# seismometer.net
KiCad netlist of a schematic drawn in EAGLE
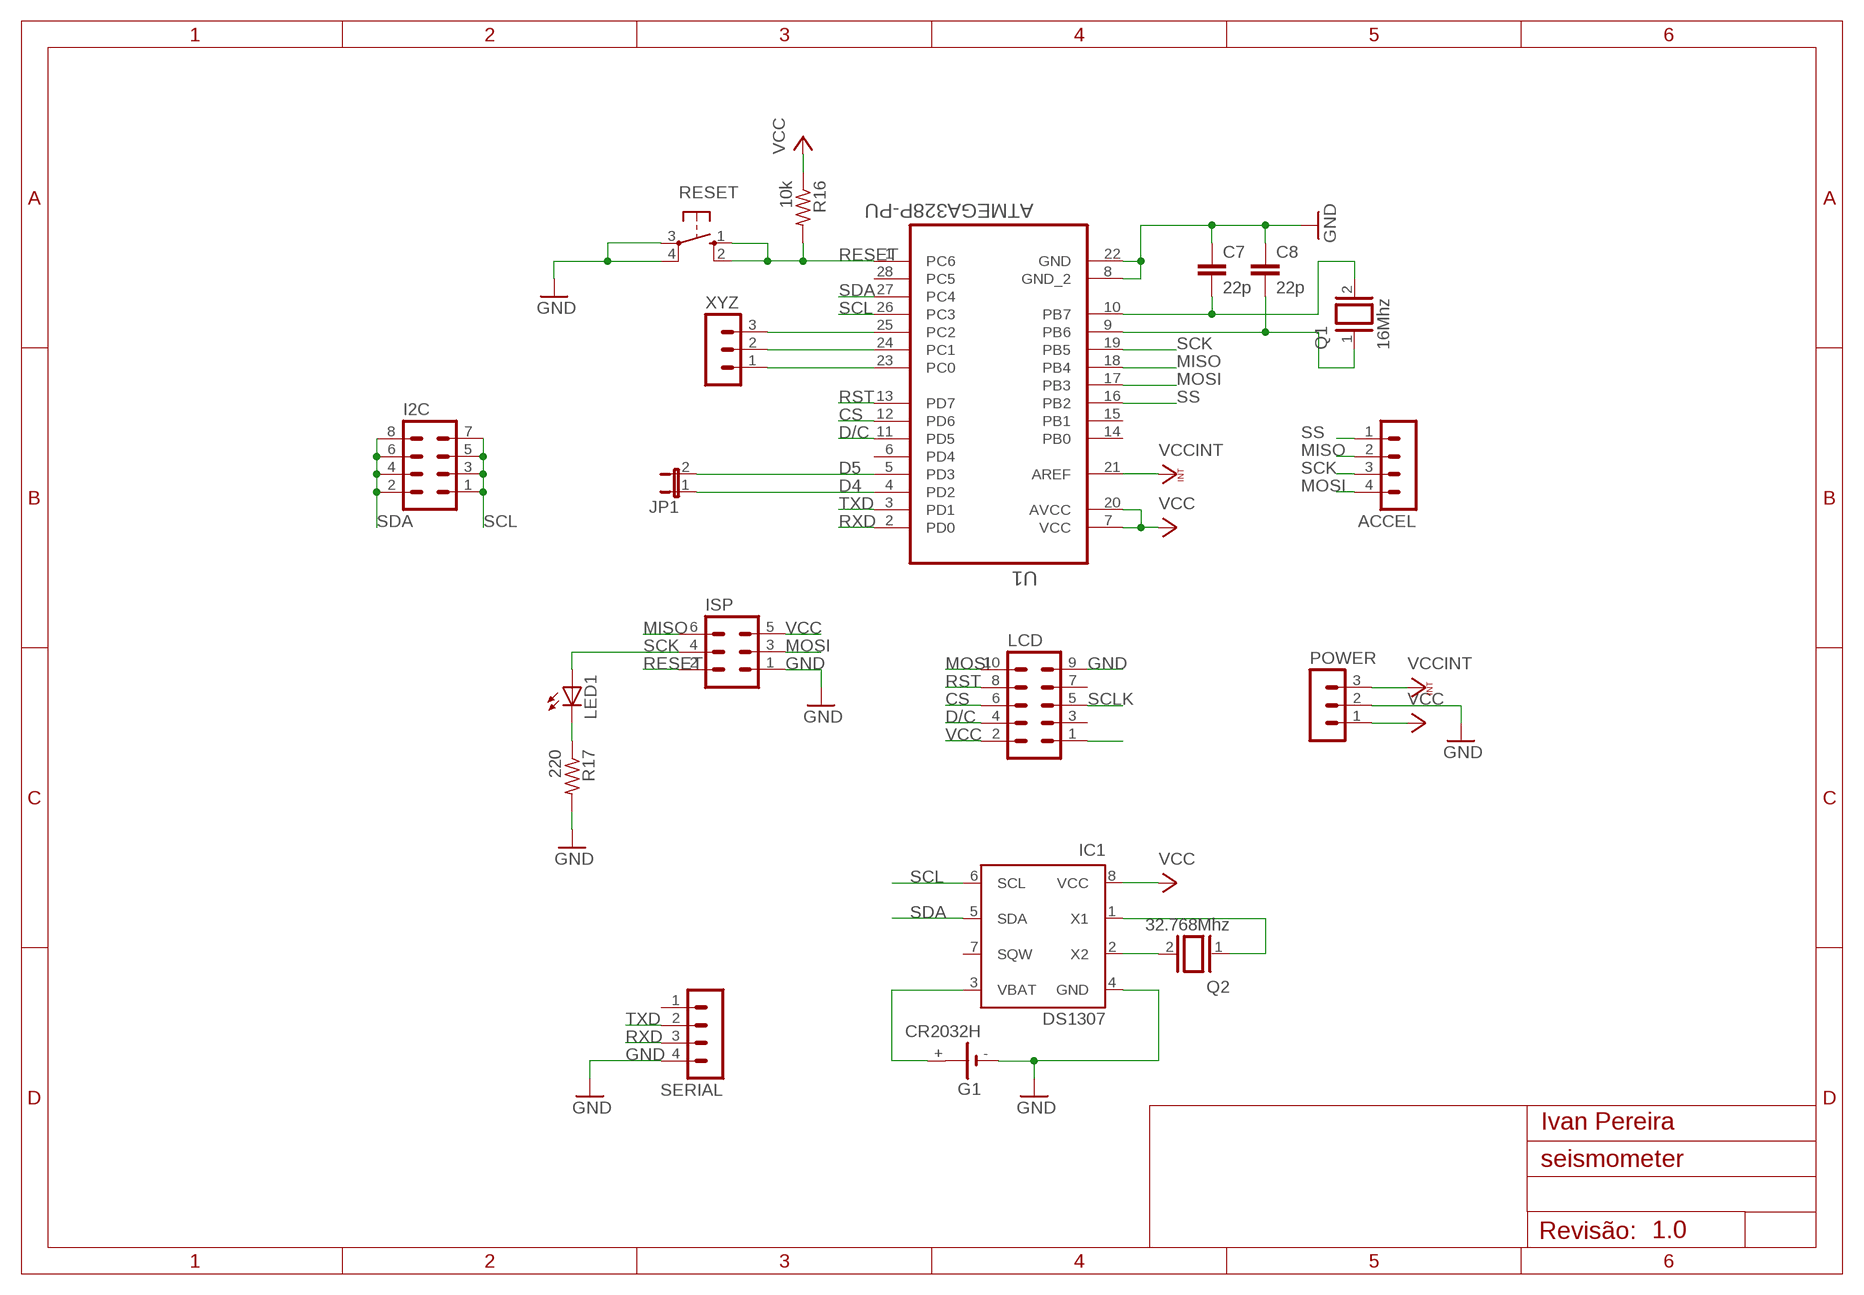
[diagram p0: schematic, sheet 1]

(export (version "E")
  (design (tool "Eeschema 10.0.6"))
  (components
    (comp (ref "ACCEL")
      (value "MA04-1")
      (footprint "eagle-import:MA04-1")
      (libsource (lib "eagle-import") (part "MA04-1"))
    )
    (comp (ref "C7")
      (value "22p")
      (footprint "eagle-import:C050-025X075")
      (libsource (lib "eagle-import") (part "C-EU050-025X075"))
    )
    (comp (ref "C8")
      (value "22p")
      (footprint "eagle-import:C050-025X075")
      (libsource (lib "eagle-import") (part "C-EU050-025X075"))
    )
    (comp (ref "G1")
      (value "CR2032H")
      (footprint "eagle-import:CR2032H")
      (libsource (lib "eagle-import") (part "CR2032H"))
    )
    (comp (ref "I2C")
      (value "MA04-2")
      (footprint "eagle-import:MA04-2")
      (libsource (lib "eagle-import") (part "MA04-2"))
    )
    (comp (ref "IC1")
      (value "DS1307")
      (footprint "eagle-import:DIL08")
      (libsource (lib "eagle-import") (part "DS1307"))
    )
    (comp (ref "ISP")
      (value "MA03-2")
      (footprint "eagle-import:MA03-2")
      (libsource (lib "eagle-import") (part "MA03-2"))
    )
    (comp (ref "JP1")
      (value "JP1E")
      (footprint "eagle-import:JP1")
      (libsource (lib "eagle-import") (part "JP1E"))
    )
    (comp (ref "LCD")
      (value "MA05-2")
      (footprint "eagle-import:MA05-2")
      (libsource (lib "eagle-import") (part "MA05-2"))
    )
    (comp (ref "LED1")
      (value "LED3MM")
      (footprint "eagle-import:LED3MM")
      (libsource (lib "eagle-import") (part "LED3MM"))
    )
    (comp (ref "POWER")
      (value "MA03-1")
      (footprint "eagle-import:MA03-1")
      (libsource (lib "eagle-import") (part "MA03-1"))
    )
    (comp (ref "Q1")
      (value "16Mhz")
      (footprint "eagle-import:QS")
      (libsource (lib "eagle-import") (part "XTAL/S"))
    )
    (comp (ref "Q2")
      (value "32.768Mhz")
      (footprint "eagle-import:QS")
      (libsource (lib "eagle-import") (part "XTAL/S"))
    )
    (comp (ref "R16")
      (value "10k")
      (footprint "eagle-import:0207_12")
      (libsource (lib "eagle-import") (part "R-US_0207/12"))
    )
    (comp (ref "R17")
      (value "220")
      (footprint "eagle-import:0207_12")
      (libsource (lib "eagle-import") (part "R-US_0207/12"))
    )
    (comp (ref "RESET")
      (value "10-XX")
      (footprint "eagle-import:B3F-10XX")
      (fields (field (name "MPN") "B3F-1000"))
      (libsource (lib "eagle-import") (part "10-XX"))
    )
    (comp (ref "SERIAL")
      (value "MA04-1")
      (footprint "eagle-import:MA04-1")
      (libsource (lib "eagle-import") (part "MA04-1"))
    )
    (comp (ref "U1")
      (value "ATMEGA328P-PU")
      (footprint "eagle-import:DIP254P762X457-28")
      (libsource (lib "eagle-import") (part "ATMEGA328P-PU"))
    )
    (comp (ref "XYZ")
      (value "MA03-1")
      (footprint "eagle-import:MA03-1")
      (libsource (lib "eagle-import") (part "MA03-1"))
    )
  )
  (nets
    (net (code "1") (name "/CS") (class "Default")
      (node (ref "LCD") (pin "6") (pinfunction "6_6") (pintype "passive"))
      (node (ref "U1") (pin "12") (pinfunction "PD6_12") (pintype "bidirectional"))
    )
    (net (code "2") (name "/D4") (class "Default")
      (node (ref "JP1") (pin "1") (pinfunction "1_1") (pintype "passive"))
      (node (ref "U1") (pin "4") (pinfunction "PD2_4") (pintype "bidirectional"))
    )
    (net (code "3") (name "/D5") (class "Default")
      (node (ref "JP1") (pin "2") (pinfunction "2_2") (pintype "passive"))
      (node (ref "U1") (pin "5") (pinfunction "PD3_5") (pintype "bidirectional"))
    )
    (net (code "4") (name "/D{slash}C") (class "Default")
      (node (ref "LCD") (pin "4") (pinfunction "4_4") (pintype "passive"))
      (node (ref "U1") (pin "11") (pinfunction "PD5_11") (pintype "bidirectional"))
    )
    (net (code "5") (name "/MISO") (class "Default")
      (node (ref "ACCEL") (pin "2") (pinfunction "2_2") (pintype "passive"))
      (node (ref "ISP") (pin "6") (pinfunction "6_6") (pintype "passive"))
      (node (ref "U1") (pin "18") (pinfunction "PB4_18") (pintype "bidirectional"))
    )
    (net (code "6") (name "/MOSI") (class "Default")
      (node (ref "ACCEL") (pin "4") (pinfunction "4_4") (pintype "passive"))
      (node (ref "ISP") (pin "3") (pinfunction "3_3") (pintype "passive"))
      (node (ref "LCD") (pin "10") (pinfunction "10_10") (pintype "passive"))
      (node (ref "U1") (pin "17") (pinfunction "PB3_17") (pintype "bidirectional"))
    )
    (net (code "7") (name "/RESET") (class "Default")
      (node (ref "ISP") (pin "2") (pinfunction "2_2") (pintype "passive"))
      (node (ref "R16") (pin "2") (pinfunction "2_2") (pintype "passive"))
      (node (ref "RESET") (pin "1") (pinfunction "S_1") (pintype "passive"))
      (node (ref "RESET") (pin "2") (pinfunction "S1_2") (pintype "passive"))
      (node (ref "U1") (pin "1") (pinfunction "PC6_1") (pintype "bidirectional"))
    )
    (net (code "8") (name "/RST") (class "Default")
      (node (ref "LCD") (pin "8") (pinfunction "8_8") (pintype "passive"))
      (node (ref "U1") (pin "13") (pinfunction "PD7_13") (pintype "bidirectional"))
    )
    (net (code "9") (name "/RXD") (class "Default")
      (node (ref "SERIAL") (pin "3") (pinfunction "3_3") (pintype "passive"))
      (node (ref "U1") (pin "2") (pinfunction "PD0_2") (pintype "bidirectional"))
    )
    (net (code "10") (name "/SCK") (class "Default")
      (node (ref "ACCEL") (pin "3") (pinfunction "3_3") (pintype "passive"))
      (node (ref "ISP") (pin "4") (pinfunction "4_4") (pintype "passive"))
      (node (ref "LED1") (pin "A") (pinfunction "A_A") (pintype "passive"))
      (node (ref "U1") (pin "19") (pinfunction "PB5_19") (pintype "bidirectional"))
    )
    (net (code "11") (name "/SCL") (class "Default")
      (node (ref "I2C") (pin "1") (pinfunction "1_1") (pintype "passive"))
      (node (ref "I2C") (pin "3") (pinfunction "3_3") (pintype "passive"))
      (node (ref "I2C") (pin "5") (pinfunction "5_5") (pintype "passive"))
      (node (ref "I2C") (pin "7") (pinfunction "7_7") (pintype "passive"))
      (node (ref "IC1") (pin "6") (pinfunction "SCL_6") (pintype "input"))
      (node (ref "U1") (pin "26") (pinfunction "PC3_26") (pintype "bidirectional"))
    )
    (net (code "12") (name "/SCLK") (class "Default")
      (node (ref "LCD") (pin "5") (pinfunction "5_5") (pintype "passive"))
    )
    (net (code "13") (name "/SDA") (class "Default")
      (node (ref "I2C") (pin "2") (pinfunction "2_2") (pintype "passive"))
      (node (ref "I2C") (pin "4") (pinfunction "4_4") (pintype "passive"))
      (node (ref "I2C") (pin "6") (pinfunction "6_6") (pintype "passive"))
      (node (ref "I2C") (pin "8") (pinfunction "8_8") (pintype "passive"))
      (node (ref "IC1") (pin "5") (pinfunction "SDA_5") (pintype "bidirectional"))
      (node (ref "U1") (pin "27") (pinfunction "PC4_27") (pintype "bidirectional"))
    )
    (net (code "14") (name "/SS") (class "Default")
      (node (ref "ACCEL") (pin "1") (pinfunction "1_1") (pintype "passive"))
      (node (ref "U1") (pin "16") (pinfunction "PB2_16") (pintype "bidirectional"))
    )
    (net (code "15") (name "/TXD") (class "Default")
      (node (ref "SERIAL") (pin "2") (pinfunction "2_2") (pintype "passive"))
      (node (ref "U1") (pin "3") (pinfunction "PD1_3") (pintype "bidirectional"))
    )
    (net (code "16") (name "GND") (class "Default")
      (node (ref "C7") (pin "1") (pinfunction "1_1") (pintype "passive"))
      (node (ref "C8") (pin "1") (pinfunction "1_1") (pintype "passive"))
      (node (ref "G1") (pin "-") (pinfunction "-_-") (pintype "passive"))
      (node (ref "IC1") (pin "4") (pinfunction "GND_4") (pintype "power_in"))
      (node (ref "ISP") (pin "1") (pinfunction "1_1") (pintype "passive"))
      (node (ref "LCD") (pin "9") (pinfunction "9_9") (pintype "passive"))
      (node (ref "POWER") (pin "2") (pinfunction "2_2") (pintype "passive"))
      (node (ref "R17") (pin "2") (pinfunction "2_2") (pintype "passive"))
      (node (ref "RESET") (pin "3") (pinfunction "P_3") (pintype "passive"))
      (node (ref "RESET") (pin "4") (pinfunction "P1_4") (pintype "passive"))
      (node (ref "SERIAL") (pin "4") (pinfunction "4_4") (pintype "passive"))
      (node (ref "U1") (pin "22") (pinfunction "GND_22") (pintype "passive"))
      (node (ref "U1") (pin "8") (pinfunction "GND_2_8") (pintype "passive"))
    )
    (net (code "17") (name "Net-(IC1-VBAT)") (class "Default")
      (node (ref "G1") (pin "+") (pinfunction "+_+") (pintype "passive"))
      (node (ref "IC1") (pin "3") (pinfunction "VBAT_3") (pintype "passive"))
    )
    (net (code "18") (name "Net-(IC1-X1)") (class "Default")
      (node (ref "IC1") (pin "1") (pinfunction "X1_1") (pintype "input"))
      (node (ref "Q2") (pin "1") (pinfunction "1_1") (pintype "passive"))
    )
    (net (code "19") (name "Net-(IC1-X2)") (class "Default")
      (node (ref "IC1") (pin "2") (pinfunction "X2_2") (pintype "output"))
      (node (ref "Q2") (pin "2") (pinfunction "2_2") (pintype "passive"))
    )
    (net (code "20") (name "Net-(LED1-C)") (class "Default")
      (node (ref "LED1") (pin "K") (pinfunction "C_K") (pintype "passive"))
      (node (ref "R17") (pin "1") (pinfunction "1_1") (pintype "passive"))
    )
    (net (code "21") (name "Net-(U1-PB6)") (class "Default")
      (node (ref "C8") (pin "2") (pinfunction "2_2") (pintype "passive"))
      (node (ref "Q1") (pin "1") (pinfunction "1_1") (pintype "passive"))
      (node (ref "U1") (pin "9") (pinfunction "PB6_9") (pintype "bidirectional"))
    )
    (net (code "22") (name "Net-(U1-PB7)") (class "Default")
      (node (ref "C7") (pin "2") (pinfunction "2_2") (pintype "passive"))
      (node (ref "Q1") (pin "2") (pinfunction "2_2") (pintype "passive"))
      (node (ref "U1") (pin "10") (pinfunction "PB7_10") (pintype "bidirectional"))
    )
    (net (code "23") (name "Net-(U1-PC0)") (class "Default")
      (node (ref "U1") (pin "23") (pinfunction "PC0_23") (pintype "bidirectional"))
      (node (ref "XYZ") (pin "1") (pinfunction "1_1") (pintype "passive"))
    )
    (net (code "24") (name "Net-(U1-PC1)") (class "Default")
      (node (ref "U1") (pin "24") (pinfunction "PC1_24") (pintype "bidirectional"))
      (node (ref "XYZ") (pin "2") (pinfunction "2_2") (pintype "passive"))
    )
    (net (code "25") (name "Net-(U1-PC2)") (class "Default")
      (node (ref "U1") (pin "25") (pinfunction "PC2_25") (pintype "bidirectional"))
      (node (ref "XYZ") (pin "3") (pinfunction "3_3") (pintype "passive"))
    )
    (net (code "26") (name "VCC") (class "Default")
      (node (ref "IC1") (pin "8") (pinfunction "VCC_8") (pintype "power_in"))
      (node (ref "ISP") (pin "5") (pinfunction "5_5") (pintype "passive"))
      (node (ref "LCD") (pin "2") (pinfunction "2_2") (pintype "passive"))
      (node (ref "POWER") (pin "1") (pinfunction "1_1") (pintype "passive"))
      (node (ref "R16") (pin "1") (pinfunction "1_1") (pintype "passive"))
      (node (ref "U1") (pin "20") (pinfunction "AVCC_20") (pintype "power_in"))
      (node (ref "U1") (pin "7") (pinfunction "VCC_7") (pintype "power_in"))
    )
    (net (code "27") (name "VCCINT") (class "Default")
      (node (ref "POWER") (pin "3") (pinfunction "3_3") (pintype "passive"))
      (node (ref "U1") (pin "21") (pinfunction "AREF_21") (pintype "input"))
    )
    (net (code "28") (name "unconnected-(G1-+-Pad+@1)") (class "Default")
      (node (ref "G1") (pin "+@1") (pinfunction "+_+@1") (pintype "passive"))
    )
    (net (code "29") (name "unconnected-(IC1-SQW-Pad7)") (class "Default")
      (node (ref "IC1") (pin "7") (pinfunction "SQW_7") (pintype "open_collector"))
    )
    (net (code "30") (name "unconnected-(LCD-Pad1)") (class "Default")
      (node (ref "LCD") (pin "1") (pinfunction "1_1") (pintype "passive"))
    )
    (net (code "31") (name "unconnected-(LCD-Pad3)") (class "Default")
      (node (ref "LCD") (pin "3") (pinfunction "3_3") (pintype "passive"))
    )
    (net (code "32") (name "unconnected-(LCD-Pad7)") (class "Default")
      (node (ref "LCD") (pin "7") (pinfunction "7_7") (pintype "passive"))
    )
    (net (code "33") (name "unconnected-(SERIAL-Pad1)") (class "Default")
      (node (ref "SERIAL") (pin "1") (pinfunction "1_1") (pintype "passive"))
    )
    (net (code "34") (name "unconnected-(U1-PB0-Pad14)") (class "Default")
      (node (ref "U1") (pin "14") (pinfunction "PB0_14") (pintype "bidirectional"))
    )
    (net (code "35") (name "unconnected-(U1-PB1-Pad15)") (class "Default")
      (node (ref "U1") (pin "15") (pinfunction "PB1_15") (pintype "bidirectional"))
    )
    (net (code "36") (name "unconnected-(U1-PC5-Pad28)") (class "Default")
      (node (ref "U1") (pin "28") (pinfunction "PC5_28") (pintype "bidirectional"))
    )
    (net (code "37") (name "unconnected-(U1-PD4-Pad6)") (class "Default")
      (node (ref "U1") (pin "6") (pinfunction "PD4_6") (pintype "bidirectional"))
    )
  )
)
